# s1_sch.net
KiCad netlist of a schematic drawn in EasyEDA
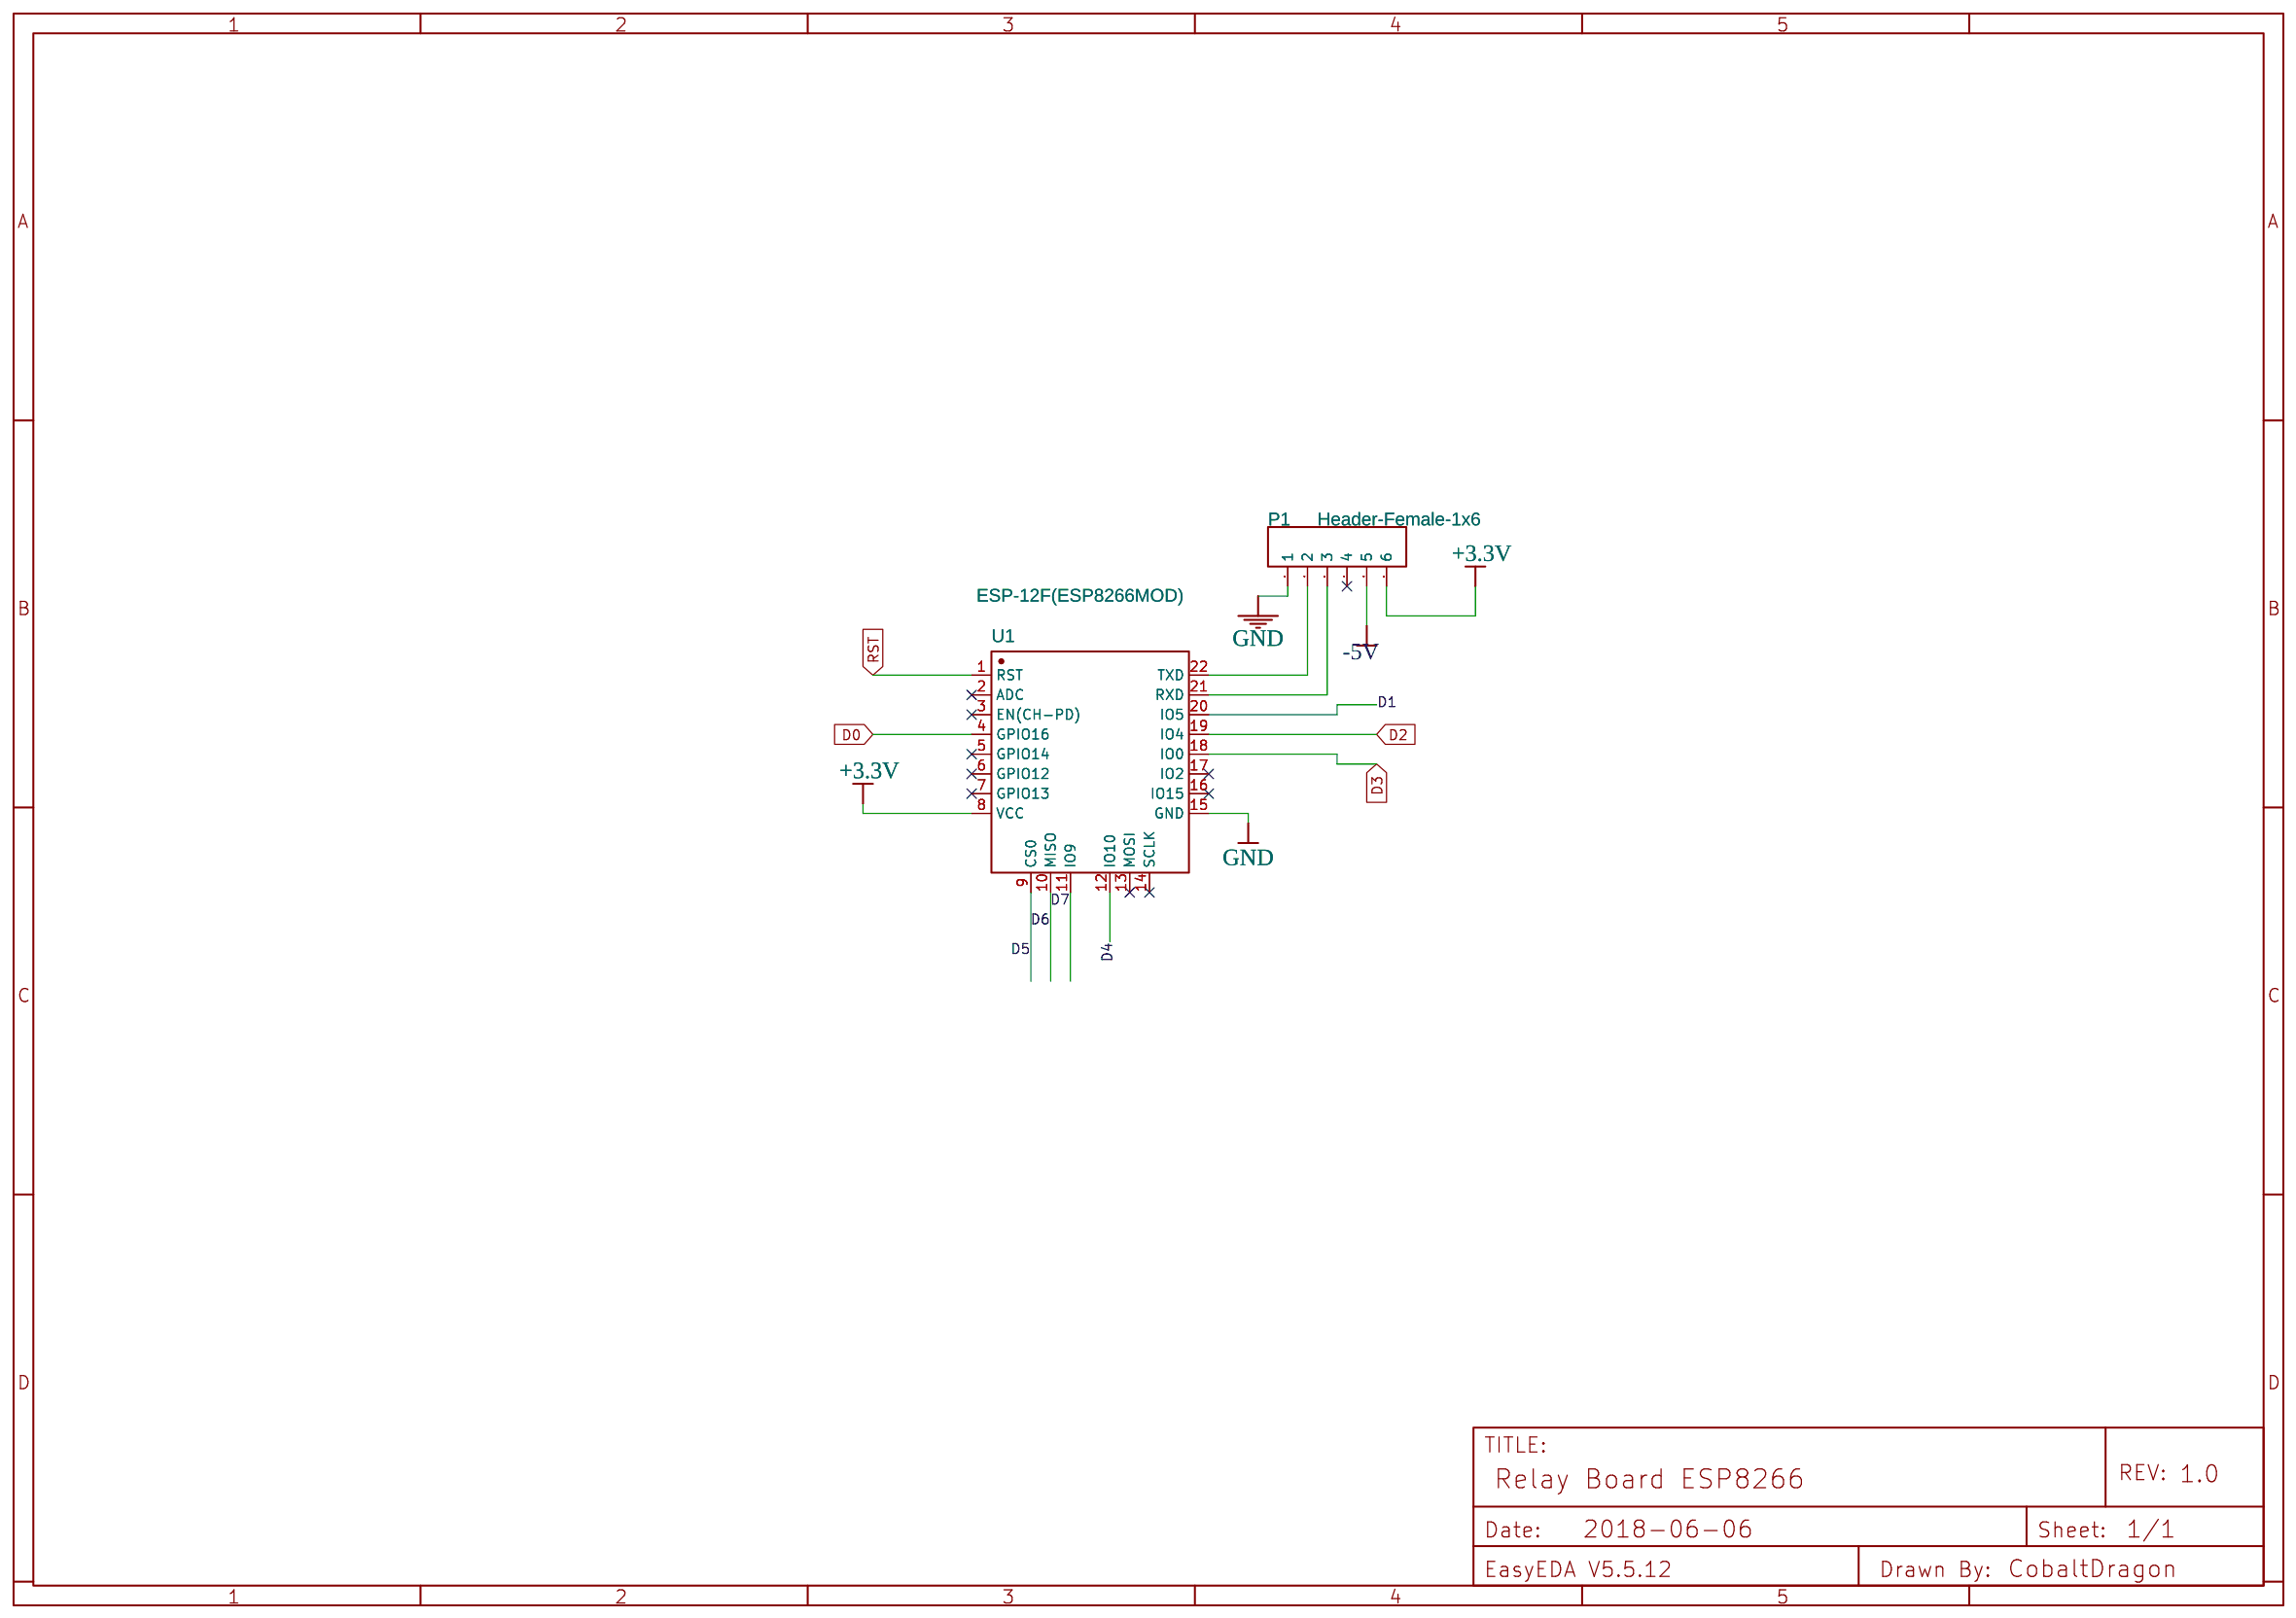
[diagram p0: schematic sheet]

(export (version "E")
  (design (tool "Eeschema 10.0.6"))
  (components
    (comp (ref "P1")
      (value "Header-Female-1x6")
      (fields
        (field (name "BOM_Manufacturer Part") "Female header 1*6p")
        (field (name "BOM_Supplier Part") "C40877")
      )
      (libsource (lib "") (part "Unknown_670_275"))
    )
    (comp (ref "U1")
      (value "ESP-12F(ESP8266MOD)")
      (fields (field (name "BOM_Supplier Part") "C82891"))
      (libsource (lib "") (part "Unknown_545_375"))
    )
  )
  (nets
    (net (code "1") (name "+3.3V") (class "Default")
      (node (ref "P1") (pin "6") (pinfunction "6_6") (pintype "input"))
      (node (ref "U1") (pin "8") (pinfunction "VCC_8") (pintype "unspecified"))
    )
    (net (code "2") (name "-5V") (class "Default")
      (node (ref "P1") (pin "5") (pinfunction "5_5") (pintype "input"))
    )
    (net (code "3") (name "/D1") (class "Default")
      (node (ref "U1") (pin "20") (pinfunction "IO5_20") (pintype "unspecified"))
    )
    (net (code "4") (name "/D4") (class "Default")
      (node (ref "U1") (pin "12") (pinfunction "IO10_12") (pintype "unspecified"))
    )
    (net (code "5") (name "/D5") (class "Default")
      (node (ref "U1") (pin "9") (pinfunction "CS0_9") (pintype "unspecified"))
    )
    (net (code "6") (name "/D6") (class "Default")
      (node (ref "U1") (pin "10") (pinfunction "MISO_10") (pintype "unspecified"))
    )
    (net (code "7") (name "/D7") (class "Default")
      (node (ref "U1") (pin "11") (pinfunction "IO9_11") (pintype "unspecified"))
    )
    (net (code "8") (name "D0") (class "Default")
      (node (ref "U1") (pin "4") (pinfunction "GPIO16_4") (pintype "unspecified"))
    )
    (net (code "9") (name "D2") (class "Default")
      (node (ref "U1") (pin "19") (pinfunction "IO4_19") (pintype "unspecified"))
    )
    (net (code "10") (name "D3") (class "Default")
      (node (ref "U1") (pin "18") (pinfunction "IO0_18") (pintype "unspecified"))
    )
    (net (code "11") (name "GND") (class "Default")
      (node (ref "P1") (pin "1") (pinfunction "1_1") (pintype "input"))
      (node (ref "U1") (pin "15") (pinfunction "GND_15") (pintype "unspecified"))
    )
    (net (code "12") (name "Net-(U1-RXD)") (class "Default")
      (node (ref "P1") (pin "3") (pinfunction "3_3") (pintype "input"))
      (node (ref "U1") (pin "21") (pinfunction "RXD_21") (pintype "unspecified"))
    )
    (net (code "13") (name "Net-(U1-TXD)") (class "Default")
      (node (ref "P1") (pin "2") (pinfunction "2_2") (pintype "input"))
      (node (ref "U1") (pin "22") (pinfunction "TXD_22") (pintype "unspecified"))
    )
    (net (code "14") (name "RST") (class "Default")
      (node (ref "U1") (pin "1") (pinfunction "RST_1") (pintype "unspecified"))
    )
    (net (code "15") (name "unconnected-(P1-Pad4)") (class "Default")
      (node (ref "P1") (pin "4") (pinfunction "4_4") (pintype "input+no_connect"))
    )
    (net (code "16") (name "unconnected-(U1-ADC-Pad2)") (class "Default")
      (node (ref "U1") (pin "2") (pinfunction "ADC_2") (pintype "unspecified+no_connect"))
    )
    (net (code "17") (name "unconnected-(U1-EN(CH-PD)-Pad3)") (class "Default")
      (node (ref "U1") (pin "3") (pinfunction "EN(CH-PD)_3") (pintype "unspecified+no_connect"))
    )
    (net (code "18") (name "unconnected-(U1-GPIO12-Pad6)") (class "Default")
      (node (ref "U1") (pin "6") (pinfunction "GPIO12_6") (pintype "unspecified+no_connect"))
    )
    (net (code "19") (name "unconnected-(U1-GPIO13-Pad7)") (class "Default")
      (node (ref "U1") (pin "7") (pinfunction "GPIO13_7") (pintype "unspecified+no_connect"))
    )
    (net (code "20") (name "unconnected-(U1-GPIO14-Pad5)") (class "Default")
      (node (ref "U1") (pin "5") (pinfunction "GPIO14_5") (pintype "unspecified+no_connect"))
    )
    (net (code "21") (name "unconnected-(U1-IO2-Pad17)") (class "Default")
      (node (ref "U1") (pin "17") (pinfunction "IO2_17") (pintype "unspecified+no_connect"))
    )
    (net (code "22") (name "unconnected-(U1-IO15-Pad16)") (class "Default")
      (node (ref "U1") (pin "16") (pinfunction "IO15_16") (pintype "unspecified+no_connect"))
    )
    (net (code "23") (name "unconnected-(U1-MOSI-Pad13)") (class "Default")
      (node (ref "U1") (pin "13") (pinfunction "MOSI_13") (pintype "unspecified+no_connect"))
    )
    (net (code "24") (name "unconnected-(U1-SCLK-Pad14)") (class "Default")
      (node (ref "U1") (pin "14") (pinfunction "SCLK_14") (pintype "unspecified+no_connect"))
    )
  )
)
